# PaxInstruments-T100.net
KiCad netlist of a schematic drawn in EAGLE
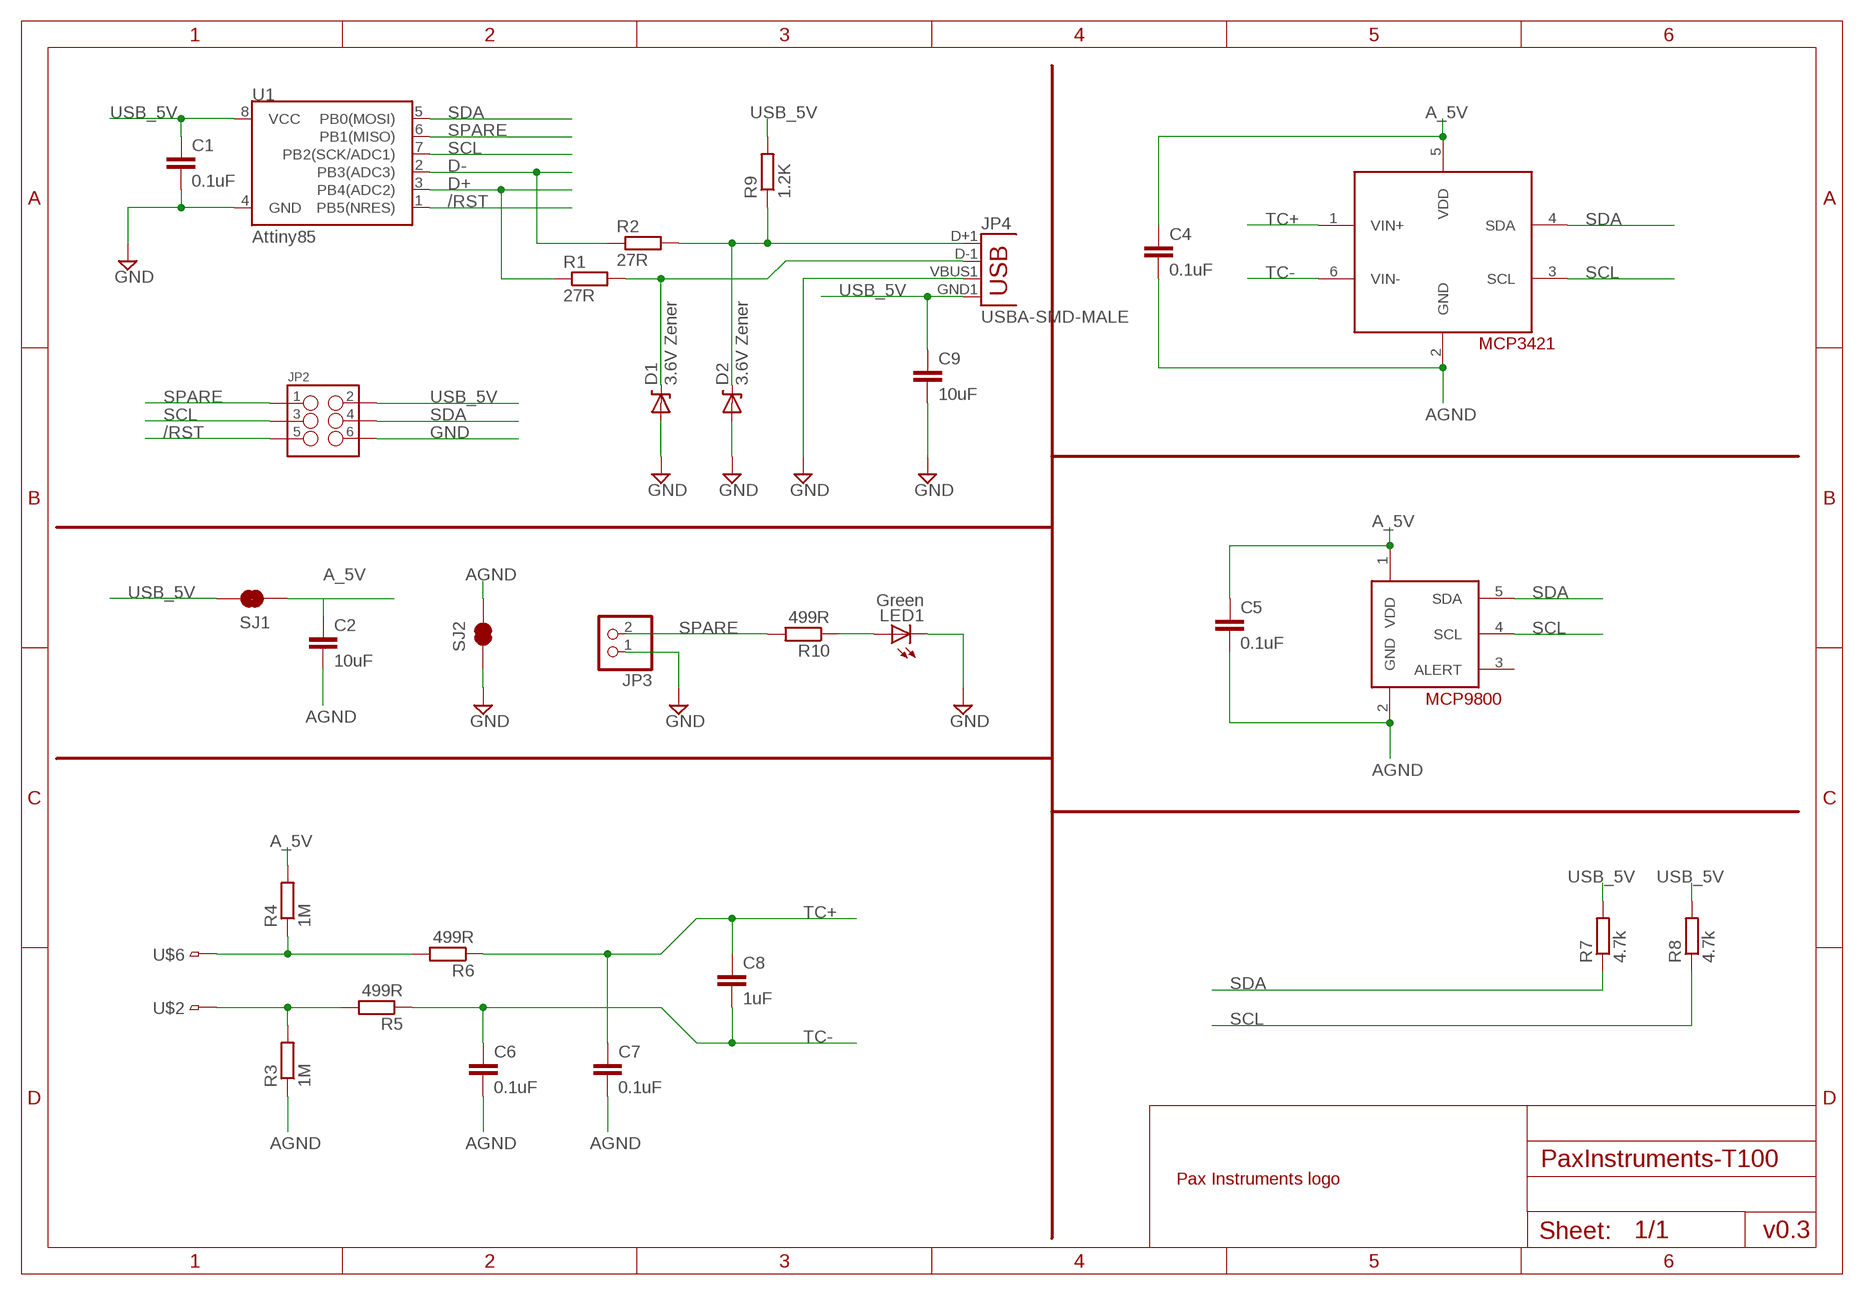
[diagram p0: schematic, sheet 1]

(export (version "E")
  (design (tool "Eeschema 10.0.6"))
  (components
    (comp (ref "C1")
      (value "0.1uF")
      (footprint "eagle-import:C0603")
      (fields
        (field (name "MF") "Yageo")
        (field (name "MPN") "CC0603JRX7R9BB104")
        (field (name "TOLERANCE") "5%")
      )
      (libsource (lib "eagle-import") (part "C-EUC0603"))
    )
    (comp (ref "C2")
      (value "10uF")
      (footprint "eagle-import:1206")
      (fields
        (field (name "MF") "Yageo")
        (field (name "MPN") "CC1206KKX5R7BB106")
        (field (name "TOLERANCE") "10%")
      )
      (libsource (lib "eagle-import") (part "CAP1206"))
    )
    (comp (ref "C4")
      (value "0.1uF")
      (footprint "eagle-import:C0603")
      (fields
        (field (name "MF") "Yageo")
        (field (name "MPN") "CC0603JRX7R9BB104")
        (field (name "TOLERANCE") "5%")
      )
      (libsource (lib "eagle-import") (part "C-EUC0603"))
    )
    (comp (ref "C5")
      (value "0.1uF")
      (footprint "eagle-import:C0603")
      (fields
        (field (name "MF") "Yageo")
        (field (name "MPN") "CC0603JRX7R9BB104")
        (field (name "TOLERANCE") "5%")
      )
      (libsource (lib "eagle-import") (part "C-EUC0603"))
    )
    (comp (ref "C6")
      (value "0.1uF")
      (footprint "eagle-import:C0603")
      (fields
        (field (name "MF") "Yageo")
        (field (name "MPN") "CC0603JRX7R9BB104")
        (field (name "TOLERANCE") "5%")
      )
      (libsource (lib "eagle-import") (part "C-EUC0603"))
    )
    (comp (ref "C7")
      (value "0.1uF")
      (footprint "eagle-import:C0603")
      (fields
        (field (name "MF") "Yageo")
        (field (name "MPN") "CC0603JRX7R9BB104")
        (field (name "TOLERANCE") "5%")
      )
      (libsource (lib "eagle-import") (part "C-EUC0603"))
    )
    (comp (ref "C8")
      (value "1uF")
      (footprint "eagle-import:C0603")
      (fields
        (field (name "MF") "Murata Electronics North America")
        (field (name "MPN") "GRM155R60J105KE19D")
        (field (name "TOLERANCE") "10%")
      )
      (libsource (lib "eagle-import") (part "C-EUC0603"))
    )
    (comp (ref "C9")
      (value "10uF")
      (footprint "eagle-import:1206")
      (fields
        (field (name "MF") "Yageo")
        (field (name "MPN") "CC1206KKX5R7BB106")
        (field (name "TOLERANCE") "10%")
      )
      (libsource (lib "eagle-import") (part "CAP1206"))
    )
    (comp (ref "D1")
      (value "3.6V Zener")
      (footprint "eagle-import:SOD-323")
      (fields (field (name "MF") "Diodes Incorporated") (field (name "MPN") "BZT52C3V6S-7-F"))
      (libsource (lib "eagle-import") (part "DIODE-ZENER-BZT52"))
    )
    (comp (ref "D2")
      (value "3.6V Zener")
      (footprint "eagle-import:SOD-323")
      (fields (field (name "MF") "Diodes Incorporated") (field (name "MPN") "BZT52C3V6S-7-F"))
      (libsource (lib "eagle-import") (part "DIODE-ZENER-BZT52"))
    )
    (comp (ref "JP2")
      (value "M03X2SMT")
      (footprint "eagle-import:2X3_SMT_POSTS")
      (fields (field (name "MF") "FCI") (field (name "MPN") "95278-101A06LF"))
      (libsource (lib "eagle-import") (part "M03X2SMT"))
    )
    (comp (ref "JP3")
      (value "HEADER-1X2ROUND")
      (footprint "eagle-import:1X02_ROUND")
      (libsource (lib "eagle-import") (part "HEADER-1X2ROUND"))
    )
    (comp (ref "JP4")
      (value "USBA-SMD-MALE")
      (footprint "eagle-import:USB-A-SMT-MALE")
      (libsource (lib "eagle-import") (part "USBA-SMD-MALE"))
    )
    (comp (ref "LED1")
      (value "Green")
      (footprint "eagle-import:LED-0603")
      (fields (field (name "MF") "Lite-On Inc.") (field (name "MPN") "LTST-C191KGKT"))
      (libsource (lib "eagle-import") (part "LED0603"))
    )
    (comp (ref "R1")
      (value "27R")
      (footprint "eagle-import:R0603")
      (fields
        (field (name "MF") "Yageo")
        (field (name "MPN") "RC0603JR-0727RL")
        (field (name "TOLERANCE") "5%")
      )
      (libsource (lib "eagle-import") (part "R-EU_R0603"))
    )
    (comp (ref "R2")
      (value "27R")
      (footprint "eagle-import:R0603")
      (fields
        (field (name "MF") "Yageo")
        (field (name "MPN") "RC0603JR-0727RL")
        (field (name "TOLERANCE") "5%")
      )
      (libsource (lib "eagle-import") (part "R-EU_R0603"))
    )
    (comp (ref "R3")
      (value "1M")
      (footprint "eagle-import:R0603")
      (fields
        (field (name "MF") "Yageo")
        (field (name "MPN") "RC0603FR-071ML")
        (field (name "TOLERANCE") "1%")
      )
      (libsource (lib "eagle-import") (part "R-EU_R0603"))
    )
    (comp (ref "R4")
      (value "1M")
      (footprint "eagle-import:R0603")
      (fields
        (field (name "MF") "Yageo")
        (field (name "MPN") "RC0603FR-071ML")
        (field (name "TOLERANCE") "1%")
      )
      (libsource (lib "eagle-import") (part "R-EU_R0603"))
    )
    (comp (ref "R5")
      (value "499R")
      (footprint "eagle-import:R0603")
      (fields
        (field (name "MF") "Yageo")
        (field (name "MPN") "RT0603DRD07499RL")
        (field (name "TOLERANCE") "0.5%")
      )
      (libsource (lib "eagle-import") (part "R-EU_R0603"))
    )
    (comp (ref "R6")
      (value "499R")
      (footprint "eagle-import:R0603")
      (fields
        (field (name "MF") "Yageo")
        (field (name "MPN") "RT0603DRD07499RL")
        (field (name "TOLERANCE") "0.5%")
      )
      (libsource (lib "eagle-import") (part "R-EU_R0603"))
    )
    (comp (ref "R7")
      (value "4.7k")
      (footprint "eagle-import:R0603")
      (fields
        (field (name "MF") "Yageo")
        (field (name "MPN") "RC0603JR-074K7L")
        (field (name "TOLERANCE") "5%")
      )
      (libsource (lib "eagle-import") (part "R-EU_R0603"))
    )
    (comp (ref "R8")
      (value "4.7k")
      (footprint "eagle-import:R0603")
      (fields
        (field (name "MF") "Yageo")
        (field (name "MPN") "RC0603JR-074K7L")
        (field (name "TOLERANCE") "5%")
      )
      (libsource (lib "eagle-import") (part "R-EU_R0603"))
    )
    (comp (ref "R9")
      (value "1.2K")
      (footprint "eagle-import:R0603")
      (fields
        (field (name "MF") "Yageo")
        (field (name "MPN") "RC0603JR-071K2L")
        (field (name "TOLERANCE") "5%")
      )
      (libsource (lib "eagle-import") (part "R-EU_R0603"))
    )
    (comp (ref "R10")
      (value "499R")
      (footprint "eagle-import:R0603")
      (fields
        (field (name "MF") "Yageo")
        (field (name "MPN") "RT0603DRD07499RL")
        (field (name "TOLERANCE") "0.5%")
      )
      (libsource (lib "eagle-import") (part "R-EU_R0603"))
    )
    (comp (ref "SJ1")
      (value "JUMPER-PAD-2-NC_BY_TRACENO_SILK")
      (footprint "eagle-import:PAD-JUMPER-2-NC_BY_TRACE_NO_SILK")
      (libsource (lib "eagle-import") (part "JUMPER-PAD-2-NC_BY_TRACENO_SILK"))
    )
    (comp (ref "SJ2")
      (value "JUMPER-PAD-2-NC_BY_TRACENO_SILK")
      (footprint "eagle-import:PAD-JUMPER-2-NC_BY_TRACE_NO_SILK")
      (libsource (lib "eagle-import") (part "JUMPER-PAD-2-NC_BY_TRACENO_SILK"))
    )
    (comp (ref "U$1")
      (value "PAX-LOGOPAX-LOGO-0.25IN")
      (footprint "eagle-import:PAX-LOGO-0.25IN")
      (libsource (lib "eagle-import") (part "PAX-LOGOPAX-LOGO-0.25IN"))
    )
    (comp (ref "U$2")
      (value "TC-MINI-SINGLE")
      (footprint "eagle-import:TC-CLIP-SINGLE")
      (fields
        (field (name "MF") "Pax Instrument")
        (field (name "MPN") "Thermo-clip2")
        (field (name "MF_1") "Pax Instruments")
        (field (name "MPN_1") "1024")
      )
      (libsource (lib "eagle-import") (part "TC-MINI-SINGLE"))
    )
    (comp (ref "U$3")
      (value "MCP3421A0")
      (footprint "eagle-import:SOT23-6")
      (fields (field (name "MF") "Microchip Technology") (field (name "MPN") "MCP3421A0T-E/CH"))
      (libsource (lib "eagle-import") (part "MCP3421"))
    )
    (comp (ref "U$4")
      (value "MCP9800A0")
      (footprint "eagle-import:SOT23-5")
      (fields (field (name "MF") "Microchip Technology") (field (name "MPN") "MCP9800A0T-M/OT"))
      (libsource (lib "eagle-import") (part "MCP9800"))
    )
    (comp (ref "U$6")
      (value "TC-MINI-SINGLE")
      (footprint "eagle-import:TC-CLIP-SINGLE")
      (fields
        (field (name "MF") "Pax Instrument")
        (field (name "MPN") "Thermo-clip2")
        (field (name "MF_1") "Pax Instruments")
        (field (name "MPN_1") "1024")
      )
      (libsource (lib "eagle-import") (part "TC-MINI-SINGLE"))
    )
    (comp (ref "U1")
      (value "Attiny85")
      (footprint "eagle-import:SO08-EIAJ")
      (fields (field (name "MF") "Atmel") (field (name "MPN") "ATTINY85-20SUR"))
      (libsource (lib "eagle-import") (part "ATTINY45TINY45-20-SMT"))
    )
  )
  (nets
    (net (code "1") (name "/AGND") (class "Default")
      (node (ref "C2") (pin "2") (pinfunction "2_2") (pintype "passive"))
      (node (ref "C4") (pin "2") (pinfunction "2_2") (pintype "passive"))
      (node (ref "C5") (pin "2") (pinfunction "2_2") (pintype "passive"))
      (node (ref "C6") (pin "2") (pinfunction "2_2") (pintype "passive"))
      (node (ref "C7") (pin "2") (pinfunction "2_2") (pintype "passive"))
      (node (ref "R3") (pin "1") (pinfunction "1_1") (pintype "passive"))
      (node (ref "SJ2") (pin "2") (pinfunction "2_2") (pintype "passive"))
      (node (ref "U$3") (pin "2") (pinfunction "GND_2") (pintype "bidirectional"))
      (node (ref "U$4") (pin "2") (pinfunction "GND_2") (pintype "bidirectional"))
    )
    (net (code "2") (name "/A_5V") (class "Default")
      (node (ref "C2") (pin "1") (pinfunction "1_1") (pintype "passive"))
      (node (ref "C4") (pin "1") (pinfunction "1_1") (pintype "passive"))
      (node (ref "C5") (pin "1") (pinfunction "1_1") (pintype "passive"))
      (node (ref "R4") (pin "2") (pinfunction "2_2") (pintype "passive"))
      (node (ref "SJ1") (pin "1") (pinfunction "1_1") (pintype "passive"))
      (node (ref "U$3") (pin "5") (pinfunction "VDD_5") (pintype "bidirectional"))
      (node (ref "U$4") (pin "1") (pinfunction "VDD_1") (pintype "bidirectional"))
    )
    (net (code "3") (name "/D+") (class "Default")
      (node (ref "R1") (pin "1") (pinfunction "1_1") (pintype "passive"))
      (node (ref "U1") (pin "3") (pinfunction "PB4(ADC2)_3") (pintype "bidirectional"))
    )
    (net (code "4") (name "/D-") (class "Default")
      (node (ref "R2") (pin "1") (pinfunction "1_1") (pintype "passive"))
      (node (ref "U1") (pin "2") (pinfunction "PB3(ADC3)_2") (pintype "bidirectional"))
    )
    (net (code "5") (name "/SCL") (class "Default")
      (node (ref "JP2") (pin "3") (pinfunction "3_3") (pintype "bidirectional"))
      (node (ref "R8") (pin "1") (pinfunction "1_1") (pintype "passive"))
      (node (ref "U$3") (pin "3") (pinfunction "SCL_3") (pintype "bidirectional"))
      (node (ref "U$4") (pin "4") (pinfunction "SCL_4") (pintype "bidirectional"))
      (node (ref "U1") (pin "7") (pinfunction "PB2(SCK/ADC1)_7") (pintype "bidirectional"))
    )
    (net (code "6") (name "/SDA") (class "Default")
      (node (ref "JP2") (pin "4") (pinfunction "4_4") (pintype "bidirectional"))
      (node (ref "R7") (pin "1") (pinfunction "1_1") (pintype "passive"))
      (node (ref "U$3") (pin "4") (pinfunction "SDA_4") (pintype "bidirectional"))
      (node (ref "U$4") (pin "5") (pinfunction "SDA_5") (pintype "bidirectional"))
      (node (ref "U1") (pin "5") (pinfunction "PB0(MOSI)_5") (pintype "bidirectional"))
    )
    (net (code "7") (name "/SPARE") (class "Default")
      (node (ref "JP2") (pin "1") (pinfunction "1_1") (pintype "bidirectional"))
      (node (ref "JP3") (pin "2") (pinfunction "2_2") (pintype "passive"))
      (node (ref "R10") (pin "2") (pinfunction "2_2") (pintype "passive"))
      (node (ref "U1") (pin "6") (pinfunction "PB1(MISO)_6") (pintype "bidirectional"))
    )
    (net (code "8") (name "/TC+") (class "Default")
      (node (ref "C7") (pin "1") (pinfunction "1_1") (pintype "passive"))
      (node (ref "C8") (pin "1") (pinfunction "1_1") (pintype "passive"))
      (node (ref "R6") (pin "1") (pinfunction "1_1") (pintype "passive"))
      (node (ref "U$3") (pin "1") (pinfunction "VIN+_1") (pintype "bidirectional"))
    )
    (net (code "9") (name "/TC-") (class "Default")
      (node (ref "C6") (pin "1") (pinfunction "1_1") (pintype "passive"))
      (node (ref "C8") (pin "2") (pinfunction "2_2") (pintype "passive"))
      (node (ref "R5") (pin "1") (pinfunction "1_1") (pintype "passive"))
      (node (ref "U$3") (pin "6") (pinfunction "VIN-_6") (pintype "bidirectional"))
    )
    (net (code "10") (name "/USB_5V") (class "Default")
      (node (ref "C1") (pin "1") (pinfunction "1_1") (pintype "passive"))
      (node (ref "C9") (pin "1") (pinfunction "1_1") (pintype "passive"))
      (node (ref "JP2") (pin "2") (pinfunction "2_2") (pintype "bidirectional"))
      (node (ref "JP4") (pin "GND1") (pinfunction "GND_GND1") (pintype "bidirectional"))
      (node (ref "R7") (pin "2") (pinfunction "2_2") (pintype "passive"))
      (node (ref "R8") (pin "2") (pinfunction "2_2") (pintype "passive"))
      (node (ref "R9") (pin "2") (pinfunction "2_2") (pintype "passive"))
      (node (ref "SJ1") (pin "2") (pinfunction "2_2") (pintype "passive"))
      (node (ref "U1") (pin "8") (pinfunction "VCC_8") (pintype "bidirectional"))
    )
    (net (code "11") (name "/{slash}RST") (class "Default")
      (node (ref "JP2") (pin "5") (pinfunction "5_5") (pintype "bidirectional"))
      (node (ref "U1") (pin "1") (pinfunction "PB5(NRES)_1") (pintype "bidirectional"))
    )
    (net (code "12") (name "GND") (class "Default")
      (node (ref "C1") (pin "2") (pinfunction "2_2") (pintype "passive"))
      (node (ref "C9") (pin "2") (pinfunction "2_2") (pintype "passive"))
      (node (ref "D1") (pin "2") (pinfunction "A_2") (pintype "passive"))
      (node (ref "D2") (pin "2") (pinfunction "A_2") (pintype "passive"))
      (node (ref "JP2") (pin "6") (pinfunction "6_6") (pintype "bidirectional"))
      (node (ref "JP3") (pin "1") (pinfunction "1_1") (pintype "passive"))
      (node (ref "JP4") (pin "VBUS1") (pinfunction "VBUS_VBUS1") (pintype "bidirectional"))
      (node (ref "LED1") (pin "C") (pinfunction "C_C") (pintype "passive"))
      (node (ref "SJ2") (pin "1") (pinfunction "1_1") (pintype "passive"))
      (node (ref "U1") (pin "4") (pinfunction "GND_4") (pintype "bidirectional"))
    )
    (net (code "13") (name "Net-(D1-C)") (class "Default")
      (node (ref "D1") (pin "1") (pinfunction "C_1") (pintype "passive"))
      (node (ref "JP4") (pin "D-1") (pinfunction "D-_D-1") (pintype "bidirectional"))
      (node (ref "R1") (pin "2") (pinfunction "2_2") (pintype "passive"))
    )
    (net (code "14") (name "Net-(D2-C)") (class "Default")
      (node (ref "D2") (pin "1") (pinfunction "C_1") (pintype "passive"))
      (node (ref "JP4") (pin "D+1") (pinfunction "D+_D+1") (pintype "bidirectional"))
      (node (ref "R2") (pin "2") (pinfunction "2_2") (pintype "passive"))
      (node (ref "R9") (pin "1") (pinfunction "1_1") (pintype "passive"))
    )
    (net (code "15") (name "Net-(LED1-PadA)") (class "Default")
      (node (ref "LED1") (pin "A") (pinfunction "A_A") (pintype "passive"))
      (node (ref "R10") (pin "1") (pinfunction "1_1") (pintype "passive"))
    )
    (net (code "16") (name "Net-(U$2-1)") (class "Default")
      (node (ref "R3") (pin "2") (pinfunction "2_2") (pintype "passive"))
      (node (ref "R5") (pin "2") (pinfunction "2_2") (pintype "passive"))
      (node (ref "U$2") (pin "P$1") (pinfunction "1_P$1") (pintype "passive"))
    )
    (net (code "17") (name "Net-(U$6-1)") (class "Default")
      (node (ref "R4") (pin "1") (pinfunction "1_1") (pintype "passive"))
      (node (ref "R6") (pin "2") (pinfunction "2_2") (pintype "passive"))
      (node (ref "U$6") (pin "P$1") (pinfunction "1_P$1") (pintype "passive"))
    )
    (net (code "18") (name "unconnected-(U$4-ALERT-Pad3)") (class "Default")
      (node (ref "U$4") (pin "3") (pinfunction "ALERT_3") (pintype "bidirectional"))
    )
  )
)
